# esc_board.net
KiCad netlist of a schematic drawn in EAGLE
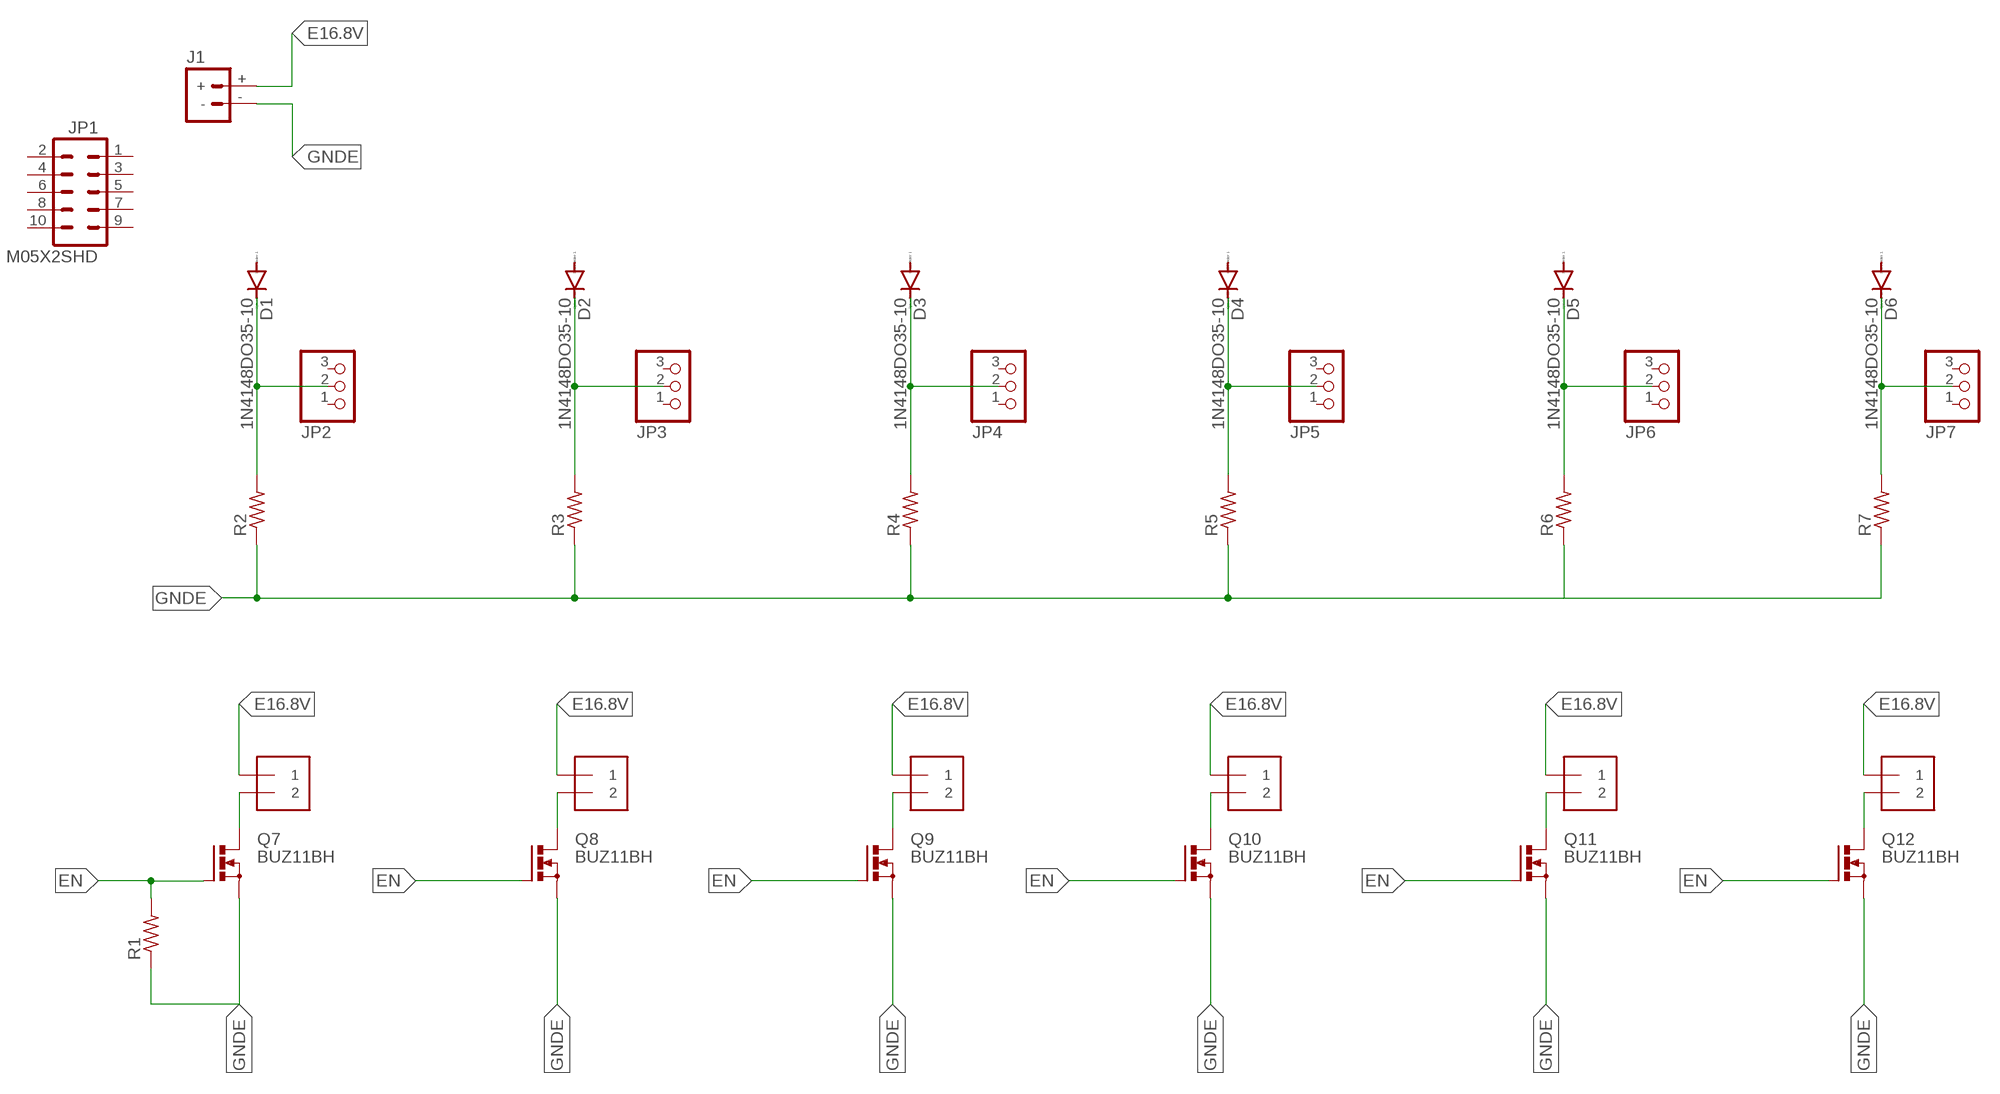
[diagram p0: schematic, sheet 1]

(export (version "E")
  (design (tool "Eeschema 10.0.6"))
  (components
    (comp (ref "D1")
      (value "1N4148DO35-10")
      (footprint "eagle-import:DO35-10")
      (libsource (lib "eagle-import") (part "1N4148DO35-10"))
    )
    (comp (ref "D2")
      (value "1N4148DO35-10")
      (footprint "eagle-import:DO35-10")
      (libsource (lib "eagle-import") (part "1N4148DO35-10"))
    )
    (comp (ref "D3")
      (value "1N4148DO35-10")
      (footprint "eagle-import:DO35-10")
      (libsource (lib "eagle-import") (part "1N4148DO35-10"))
    )
    (comp (ref "D4")
      (value "1N4148DO35-10")
      (footprint "eagle-import:DO35-10")
      (libsource (lib "eagle-import") (part "1N4148DO35-10"))
    )
    (comp (ref "D5")
      (value "1N4148DO35-10")
      (footprint "eagle-import:DO35-10")
      (libsource (lib "eagle-import") (part "1N4148DO35-10"))
    )
    (comp (ref "D6")
      (value "1N4148DO35-10")
      (footprint "eagle-import:DO35-10")
      (libsource (lib "eagle-import") (part "1N4148DO35-10"))
    )
    (comp (ref "J1")
      (value "BATTERY_CONN_DEANS")
      (footprint "eagle-import:DEANS")
      (libsource (lib "eagle-import") (part "BATTERY_CONN_DEANS"))
    )
    (comp (ref "J7")
      (value "1X2-3.5MM")
      (footprint "eagle-import:1X2-3.5MM")
      (libsource (lib "eagle-import") (part "1X2-3.5MM"))
    )
    (comp (ref "J8")
      (value "1X2-3.5MM")
      (footprint "eagle-import:1X2-3.5MM")
      (libsource (lib "eagle-import") (part "1X2-3.5MM"))
    )
    (comp (ref "J9")
      (value "1X2-3.5MM")
      (footprint "eagle-import:1X2-3.5MM")
      (libsource (lib "eagle-import") (part "1X2-3.5MM"))
    )
    (comp (ref "J10")
      (value "1X2-3.5MM")
      (footprint "eagle-import:1X2-3.5MM")
      (libsource (lib "eagle-import") (part "1X2-3.5MM"))
    )
    (comp (ref "J11")
      (value "1X2-3.5MM")
      (footprint "eagle-import:1X2-3.5MM")
      (libsource (lib "eagle-import") (part "1X2-3.5MM"))
    )
    (comp (ref "J12")
      (value "1X2-3.5MM")
      (footprint "eagle-import:1X2-3.5MM")
      (libsource (lib "eagle-import") (part "1X2-3.5MM"))
    )
    (comp (ref "JP1")
      (value "M05X2SHD")
      (footprint "eagle-import:2X5-SHROUDED")
      (libsource (lib "eagle-import") (part "M05X2SHD"))
    )
    (comp (ref "JP2")
      (value "PINHD-1X3")
      (footprint "eagle-import:1X03")
      (libsource (lib "eagle-import") (part "PINHD-1X3"))
    )
    (comp (ref "JP3")
      (value "PINHD-1X3")
      (footprint "eagle-import:1X03")
      (libsource (lib "eagle-import") (part "PINHD-1X3"))
    )
    (comp (ref "JP4")
      (value "PINHD-1X3")
      (footprint "eagle-import:1X03")
      (libsource (lib "eagle-import") (part "PINHD-1X3"))
    )
    (comp (ref "JP5")
      (value "PINHD-1X3")
      (footprint "eagle-import:1X03")
      (libsource (lib "eagle-import") (part "PINHD-1X3"))
    )
    (comp (ref "JP6")
      (value "PINHD-1X3")
      (footprint "eagle-import:1X03")
      (libsource (lib "eagle-import") (part "PINHD-1X3"))
    )
    (comp (ref "JP7")
      (value "PINHD-1X3")
      (footprint "eagle-import:1X03")
      (libsource (lib "eagle-import") (part "PINHD-1X3"))
    )
    (comp (ref "Q7")
      (value "BUZ11BH")
      (footprint "eagle-import:TO220BH")
      (libsource (lib "eagle-import") (part "BUZ11BH"))
    )
    (comp (ref "Q8")
      (value "BUZ11BH")
      (footprint "eagle-import:TO220BH")
      (libsource (lib "eagle-import") (part "BUZ11BH"))
    )
    (comp (ref "Q9")
      (value "BUZ11BH")
      (footprint "eagle-import:TO220BH")
      (libsource (lib "eagle-import") (part "BUZ11BH"))
    )
    (comp (ref "Q10")
      (value "BUZ11BH")
      (footprint "eagle-import:TO220BH")
      (libsource (lib "eagle-import") (part "BUZ11BH"))
    )
    (comp (ref "Q11")
      (value "BUZ11BH")
      (footprint "eagle-import:TO220BH")
      (libsource (lib "eagle-import") (part "BUZ11BH"))
    )
    (comp (ref "Q12")
      (value "BUZ11BH")
      (footprint "eagle-import:TO220BH")
      (libsource (lib "eagle-import") (part "BUZ11BH"))
    )
    (comp (ref "R1")
      (value "R-US_0204/7")
      (footprint "eagle-import:0204_7")
      (libsource (lib "eagle-import") (part "R-US_0204/7"))
    )
    (comp (ref "R2")
      (value "R-US_0204/7")
      (footprint "eagle-import:0204_7")
      (libsource (lib "eagle-import") (part "R-US_0204/7"))
    )
    (comp (ref "R3")
      (value "R-US_0204/7")
      (footprint "eagle-import:0204_7")
      (libsource (lib "eagle-import") (part "R-US_0204/7"))
    )
    (comp (ref "R4")
      (value "R-US_0204/7")
      (footprint "eagle-import:0204_7")
      (libsource (lib "eagle-import") (part "R-US_0204/7"))
    )
    (comp (ref "R5")
      (value "R-US_0204/7")
      (footprint "eagle-import:0204_7")
      (libsource (lib "eagle-import") (part "R-US_0204/7"))
    )
    (comp (ref "R6")
      (value "R-US_0204/7")
      (footprint "eagle-import:0204_7")
      (libsource (lib "eagle-import") (part "R-US_0204/7"))
    )
    (comp (ref "R7")
      (value "R-US_0204/7")
      (footprint "eagle-import:0204_7")
      (libsource (lib "eagle-import") (part "R-US_0204/7"))
    )
  )
  (nets
    (net (code "1") (name "E16.8V") (class "Default")
      (node (ref "J1") (pin "+") (pinfunction "+_+") (pintype "passive"))
      (node (ref "J10") (pin "1") (pinfunction "1_1") (pintype "passive"))
      (node (ref "J11") (pin "1") (pinfunction "1_1") (pintype "passive"))
      (node (ref "J12") (pin "1") (pinfunction "1_1") (pintype "passive"))
      (node (ref "J7") (pin "1") (pinfunction "1_1") (pintype "passive"))
      (node (ref "J8") (pin "1") (pinfunction "1_1") (pintype "passive"))
      (node (ref "J9") (pin "1") (pinfunction "1_1") (pintype "passive"))
    )
    (net (code "2") (name "EN") (class "Default")
      (node (ref "Q10") (pin "G") (pinfunction "G_G") (pintype "passive"))
      (node (ref "Q11") (pin "G") (pinfunction "G_G") (pintype "passive"))
      (node (ref "Q12") (pin "G") (pinfunction "G_G") (pintype "passive"))
      (node (ref "Q7") (pin "G") (pinfunction "G_G") (pintype "passive"))
      (node (ref "Q8") (pin "G") (pinfunction "G_G") (pintype "passive"))
      (node (ref "Q9") (pin "G") (pinfunction "G_G") (pintype "passive"))
      (node (ref "R1") (pin "2") (pinfunction "2_2") (pintype "passive"))
    )
    (net (code "3") (name "GNDE") (class "Default")
      (node (ref "J1") (pin "-") (pinfunction "-_-") (pintype "passive"))
      (node (ref "Q10") (pin "S") (pinfunction "S_S") (pintype "passive"))
      (node (ref "Q11") (pin "S") (pinfunction "S_S") (pintype "passive"))
      (node (ref "Q12") (pin "S") (pinfunction "S_S") (pintype "passive"))
      (node (ref "Q7") (pin "S") (pinfunction "S_S") (pintype "passive"))
      (node (ref "Q8") (pin "S") (pinfunction "S_S") (pintype "passive"))
      (node (ref "Q9") (pin "S") (pinfunction "S_S") (pintype "passive"))
      (node (ref "R1") (pin "1") (pinfunction "1_1") (pintype "passive"))
      (node (ref "R2") (pin "1") (pinfunction "1_1") (pintype "passive"))
      (node (ref "R3") (pin "1") (pinfunction "1_1") (pintype "passive"))
      (node (ref "R4") (pin "1") (pinfunction "1_1") (pintype "passive"))
      (node (ref "R5") (pin "1") (pinfunction "1_1") (pintype "passive"))
      (node (ref "R6") (pin "1") (pinfunction "1_1") (pintype "passive"))
      (node (ref "R7") (pin "1") (pinfunction "1_1") (pintype "passive"))
    )
    (net (code "4") (name "Net-(D1-PadC)") (class "Default")
      (node (ref "D1") (pin "C") (pinfunction "C_C") (pintype "passive"))
      (node (ref "JP2") (pin "2") (pinfunction "2_2") (pintype "passive"))
      (node (ref "R2") (pin "2") (pinfunction "2_2") (pintype "passive"))
    )
    (net (code "5") (name "Net-(D2-PadC)") (class "Default")
      (node (ref "D2") (pin "C") (pinfunction "C_C") (pintype "passive"))
      (node (ref "JP3") (pin "2") (pinfunction "2_2") (pintype "passive"))
      (node (ref "R3") (pin "2") (pinfunction "2_2") (pintype "passive"))
    )
    (net (code "6") (name "Net-(D3-PadC)") (class "Default")
      (node (ref "D3") (pin "C") (pinfunction "C_C") (pintype "passive"))
      (node (ref "JP4") (pin "2") (pinfunction "2_2") (pintype "passive"))
      (node (ref "R4") (pin "2") (pinfunction "2_2") (pintype "passive"))
    )
    (net (code "7") (name "Net-(D4-PadC)") (class "Default")
      (node (ref "D4") (pin "C") (pinfunction "C_C") (pintype "passive"))
      (node (ref "JP5") (pin "2") (pinfunction "2_2") (pintype "passive"))
      (node (ref "R5") (pin "2") (pinfunction "2_2") (pintype "passive"))
    )
    (net (code "8") (name "Net-(D5-PadC)") (class "Default")
      (node (ref "D5") (pin "C") (pinfunction "C_C") (pintype "passive"))
      (node (ref "JP6") (pin "2") (pinfunction "2_2") (pintype "passive"))
      (node (ref "R6") (pin "2") (pinfunction "2_2") (pintype "passive"))
    )
    (net (code "9") (name "Net-(D6-PadC)") (class "Default")
      (node (ref "D6") (pin "C") (pinfunction "C_C") (pintype "passive"))
      (node (ref "JP7") (pin "2") (pinfunction "2_2") (pintype "passive"))
      (node (ref "R7") (pin "2") (pinfunction "2_2") (pintype "passive"))
    )
    (net (code "10") (name "Net-(J7-Pad2)") (class "Default")
      (node (ref "J7") (pin "2") (pinfunction "2_2") (pintype "passive"))
      (node (ref "Q7") (pin "D") (pinfunction "D_D") (pintype "passive"))
    )
    (net (code "11") (name "Net-(J8-Pad2)") (class "Default")
      (node (ref "J8") (pin "2") (pinfunction "2_2") (pintype "passive"))
      (node (ref "Q8") (pin "D") (pinfunction "D_D") (pintype "passive"))
    )
    (net (code "12") (name "Net-(J9-Pad2)") (class "Default")
      (node (ref "J9") (pin "2") (pinfunction "2_2") (pintype "passive"))
      (node (ref "Q9") (pin "D") (pinfunction "D_D") (pintype "passive"))
    )
    (net (code "13") (name "Net-(J10-Pad2)") (class "Default")
      (node (ref "J10") (pin "2") (pinfunction "2_2") (pintype "passive"))
      (node (ref "Q10") (pin "D") (pinfunction "D_D") (pintype "passive"))
    )
    (net (code "14") (name "Net-(J11-Pad2)") (class "Default")
      (node (ref "J11") (pin "2") (pinfunction "2_2") (pintype "passive"))
      (node (ref "Q11") (pin "D") (pinfunction "D_D") (pintype "passive"))
    )
    (net (code "15") (name "Net-(J12-Pad2)") (class "Default")
      (node (ref "J12") (pin "2") (pinfunction "2_2") (pintype "passive"))
      (node (ref "Q12") (pin "D") (pinfunction "D_D") (pintype "passive"))
    )
    (net (code "16") (name "unconnected-(D1-PadA)") (class "Default")
      (node (ref "D1") (pin "A") (pinfunction "A_A") (pintype "passive"))
    )
    (net (code "17") (name "unconnected-(D2-PadA)") (class "Default")
      (node (ref "D2") (pin "A") (pinfunction "A_A") (pintype "passive"))
    )
    (net (code "18") (name "unconnected-(D3-PadA)") (class "Default")
      (node (ref "D3") (pin "A") (pinfunction "A_A") (pintype "passive"))
    )
    (net (code "19") (name "unconnected-(D4-PadA)") (class "Default")
      (node (ref "D4") (pin "A") (pinfunction "A_A") (pintype "passive"))
    )
    (net (code "20") (name "unconnected-(D5-PadA)") (class "Default")
      (node (ref "D5") (pin "A") (pinfunction "A_A") (pintype "passive"))
    )
    (net (code "21") (name "unconnected-(D6-PadA)") (class "Default")
      (node (ref "D6") (pin "A") (pinfunction "A_A") (pintype "passive"))
    )
    (net (code "22") (name "unconnected-(JP1-Pad1)") (class "Default")
      (node (ref "JP1") (pin "1") (pinfunction "1_1") (pintype "passive"))
    )
    (net (code "23") (name "unconnected-(JP1-Pad2)") (class "Default")
      (node (ref "JP1") (pin "2") (pinfunction "2_2") (pintype "passive"))
    )
    (net (code "24") (name "unconnected-(JP1-Pad3)") (class "Default")
      (node (ref "JP1") (pin "3") (pinfunction "3_3") (pintype "passive"))
    )
    (net (code "25") (name "unconnected-(JP1-Pad4)") (class "Default")
      (node (ref "JP1") (pin "4") (pinfunction "4_4") (pintype "passive"))
    )
    (net (code "26") (name "unconnected-(JP1-Pad5)") (class "Default")
      (node (ref "JP1") (pin "5") (pinfunction "5_5") (pintype "passive"))
    )
    (net (code "27") (name "unconnected-(JP1-Pad6)") (class "Default")
      (node (ref "JP1") (pin "6") (pinfunction "6_6") (pintype "passive"))
    )
    (net (code "28") (name "unconnected-(JP1-Pad7)") (class "Default")
      (node (ref "JP1") (pin "7") (pinfunction "7_7") (pintype "passive"))
    )
    (net (code "29") (name "unconnected-(JP1-Pad8)") (class "Default")
      (node (ref "JP1") (pin "8") (pinfunction "8_8") (pintype "passive"))
    )
    (net (code "30") (name "unconnected-(JP1-Pad9)") (class "Default")
      (node (ref "JP1") (pin "9") (pinfunction "9_9") (pintype "passive"))
    )
    (net (code "31") (name "unconnected-(JP1-Pad10)") (class "Default")
      (node (ref "JP1") (pin "10") (pinfunction "10_10") (pintype "passive"))
    )
    (net (code "32") (name "unconnected-(JP2-Pad1)") (class "Default")
      (node (ref "JP2") (pin "1") (pinfunction "1_1") (pintype "passive"))
    )
    (net (code "33") (name "unconnected-(JP2-Pad3)") (class "Default")
      (node (ref "JP2") (pin "3") (pinfunction "3_3") (pintype "passive"))
    )
    (net (code "34") (name "unconnected-(JP3-Pad1)") (class "Default")
      (node (ref "JP3") (pin "1") (pinfunction "1_1") (pintype "passive"))
    )
    (net (code "35") (name "unconnected-(JP3-Pad3)") (class "Default")
      (node (ref "JP3") (pin "3") (pinfunction "3_3") (pintype "passive"))
    )
    (net (code "36") (name "unconnected-(JP4-Pad1)") (class "Default")
      (node (ref "JP4") (pin "1") (pinfunction "1_1") (pintype "passive"))
    )
    (net (code "37") (name "unconnected-(JP4-Pad3)") (class "Default")
      (node (ref "JP4") (pin "3") (pinfunction "3_3") (pintype "passive"))
    )
    (net (code "38") (name "unconnected-(JP5-Pad1)") (class "Default")
      (node (ref "JP5") (pin "1") (pinfunction "1_1") (pintype "passive"))
    )
    (net (code "39") (name "unconnected-(JP5-Pad3)") (class "Default")
      (node (ref "JP5") (pin "3") (pinfunction "3_3") (pintype "passive"))
    )
    (net (code "40") (name "unconnected-(JP6-Pad1)") (class "Default")
      (node (ref "JP6") (pin "1") (pinfunction "1_1") (pintype "passive"))
    )
    (net (code "41") (name "unconnected-(JP6-Pad3)") (class "Default")
      (node (ref "JP6") (pin "3") (pinfunction "3_3") (pintype "passive"))
    )
    (net (code "42") (name "unconnected-(JP7-Pad1)") (class "Default")
      (node (ref "JP7") (pin "1") (pinfunction "1_1") (pintype "passive"))
    )
    (net (code "43") (name "unconnected-(JP7-Pad3)") (class "Default")
      (node (ref "JP7") (pin "3") (pinfunction "3_3") (pintype "passive"))
    )
  )
)
